# 5V_AC-DC_Regulator.net
KiCad netlist of a schematic drawn in EAGLE
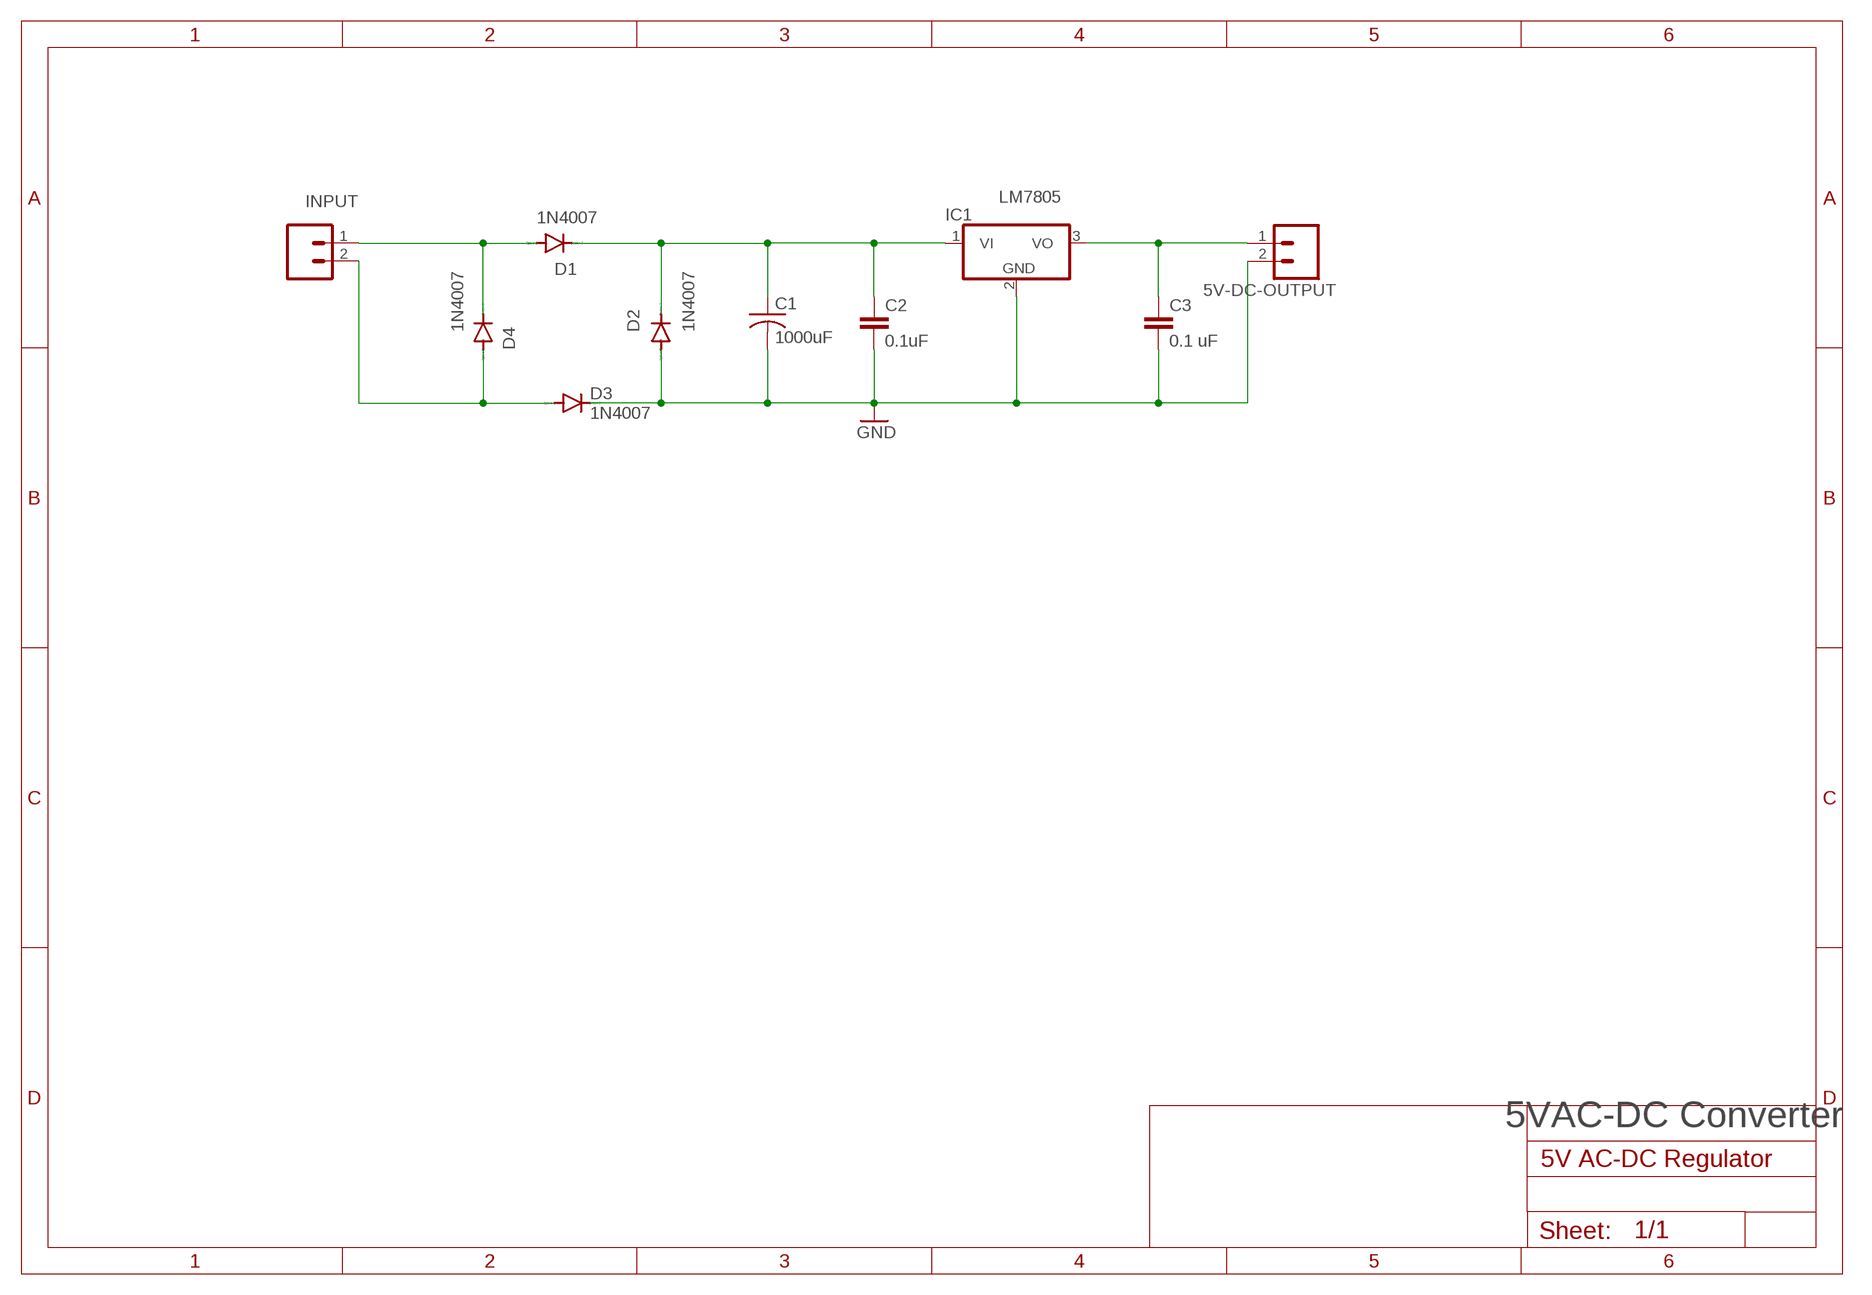
[diagram p0: schematic, sheet 1]

(export (version "E")
  (design (tool "Eeschema 10.0.6"))
  (components
    (comp (ref "5V-DC-OUTPUT")
      (value "M02")
      (footprint "eagle-import:02P")
      (libsource (lib "eagle-import") (part "M02"))
    )
    (comp (ref "C1")
      (value "1000uF")
      (footprint "eagle-import:C025-024X044")
      (libsource (lib "eagle-import") (part "C-US025-024X044"))
    )
    (comp (ref "C2")
      (value "0.1uF")
      (footprint "eagle-import:C025-025X050")
      (libsource (lib "eagle-import") (part "C-EU025-025X050"))
    )
    (comp (ref "C3")
      (value "0.1 uF")
      (footprint "eagle-import:C025-025X050")
      (libsource (lib "eagle-import") (part "C-EU025-025X050"))
    )
    (comp (ref "D1")
      (value "1N4007")
      (footprint "eagle-import:DO41-10")
      (libsource (lib "eagle-import") (part "1N4004"))
    )
    (comp (ref "D2")
      (value "1N4007")
      (footprint "eagle-import:DO41-10")
      (libsource (lib "eagle-import") (part "1N4004"))
    )
    (comp (ref "D3")
      (value "1N4007")
      (footprint "eagle-import:DO41-10")
      (libsource (lib "eagle-import") (part "1N4004"))
    )
    (comp (ref "D4")
      (value "1N4007")
      (footprint "eagle-import:DO41-10")
      (libsource (lib "eagle-import") (part "1N4004"))
    )
    (comp (ref "IC1")
      (value "LM7805")
      (footprint "eagle-import:TO220V")
      (libsource (lib "eagle-import") (part "78TV6"))
    )
    (comp (ref "INPUT")
      (value "M02")
      (footprint "eagle-import:02P")
      (libsource (lib "eagle-import") (part "M02"))
    )
  )
  (nets
    (net (code "1") (name "GND") (class "Default")
      (node (ref "5V-DC-OUTPUT") (pin "2") (pinfunction "2_2") (pintype "passive"))
      (node (ref "C1") (pin "2") (pinfunction "2_2") (pintype "passive"))
      (node (ref "C2") (pin "2") (pinfunction "2_2") (pintype "passive"))
      (node (ref "C3") (pin "2") (pinfunction "2_2") (pintype "passive"))
      (node (ref "D2") (pin "A") (pinfunction "A_A") (pintype "passive"))
      (node (ref "D3") (pin "C") (pinfunction "C_C") (pintype "passive"))
      (node (ref "IC1") (pin "2") (pinfunction "GND_2") (pintype "passive"))
    )
    (net (code "2") (name "Net-(D1-PadA)") (class "Default")
      (node (ref "D1") (pin "A") (pinfunction "A_A") (pintype "passive"))
      (node (ref "D4") (pin "C") (pinfunction "C_C") (pintype "passive"))
      (node (ref "INPUT") (pin "1") (pinfunction "1_1") (pintype "passive"))
    )
    (net (code "3") (name "Net-(D3-PadA)") (class "Default")
      (node (ref "D3") (pin "A") (pinfunction "A_A") (pintype "passive"))
      (node (ref "D4") (pin "A") (pinfunction "A_A") (pintype "passive"))
      (node (ref "INPUT") (pin "2") (pinfunction "2_2") (pintype "passive"))
    )
    (net (code "4") (name "Net-(IC1-VI)") (class "Default")
      (node (ref "C1") (pin "1") (pinfunction "1_1") (pintype "passive"))
      (node (ref "C2") (pin "1") (pinfunction "1_1") (pintype "passive"))
      (node (ref "D1") (pin "C") (pinfunction "C_C") (pintype "passive"))
      (node (ref "D2") (pin "C") (pinfunction "C_C") (pintype "passive"))
      (node (ref "IC1") (pin "1") (pinfunction "VI_1") (pintype "input"))
    )
    (net (code "5") (name "Net-(IC1-VO)") (class "Default")
      (node (ref "5V-DC-OUTPUT") (pin "1") (pinfunction "1_1") (pintype "passive"))
      (node (ref "C3") (pin "1") (pinfunction "1_1") (pintype "passive"))
      (node (ref "IC1") (pin "3") (pinfunction "VO_3") (pintype "passive"))
    )
  )
)
